# psu.net
KiCad netlist of a schematic drawn in Altium Designer
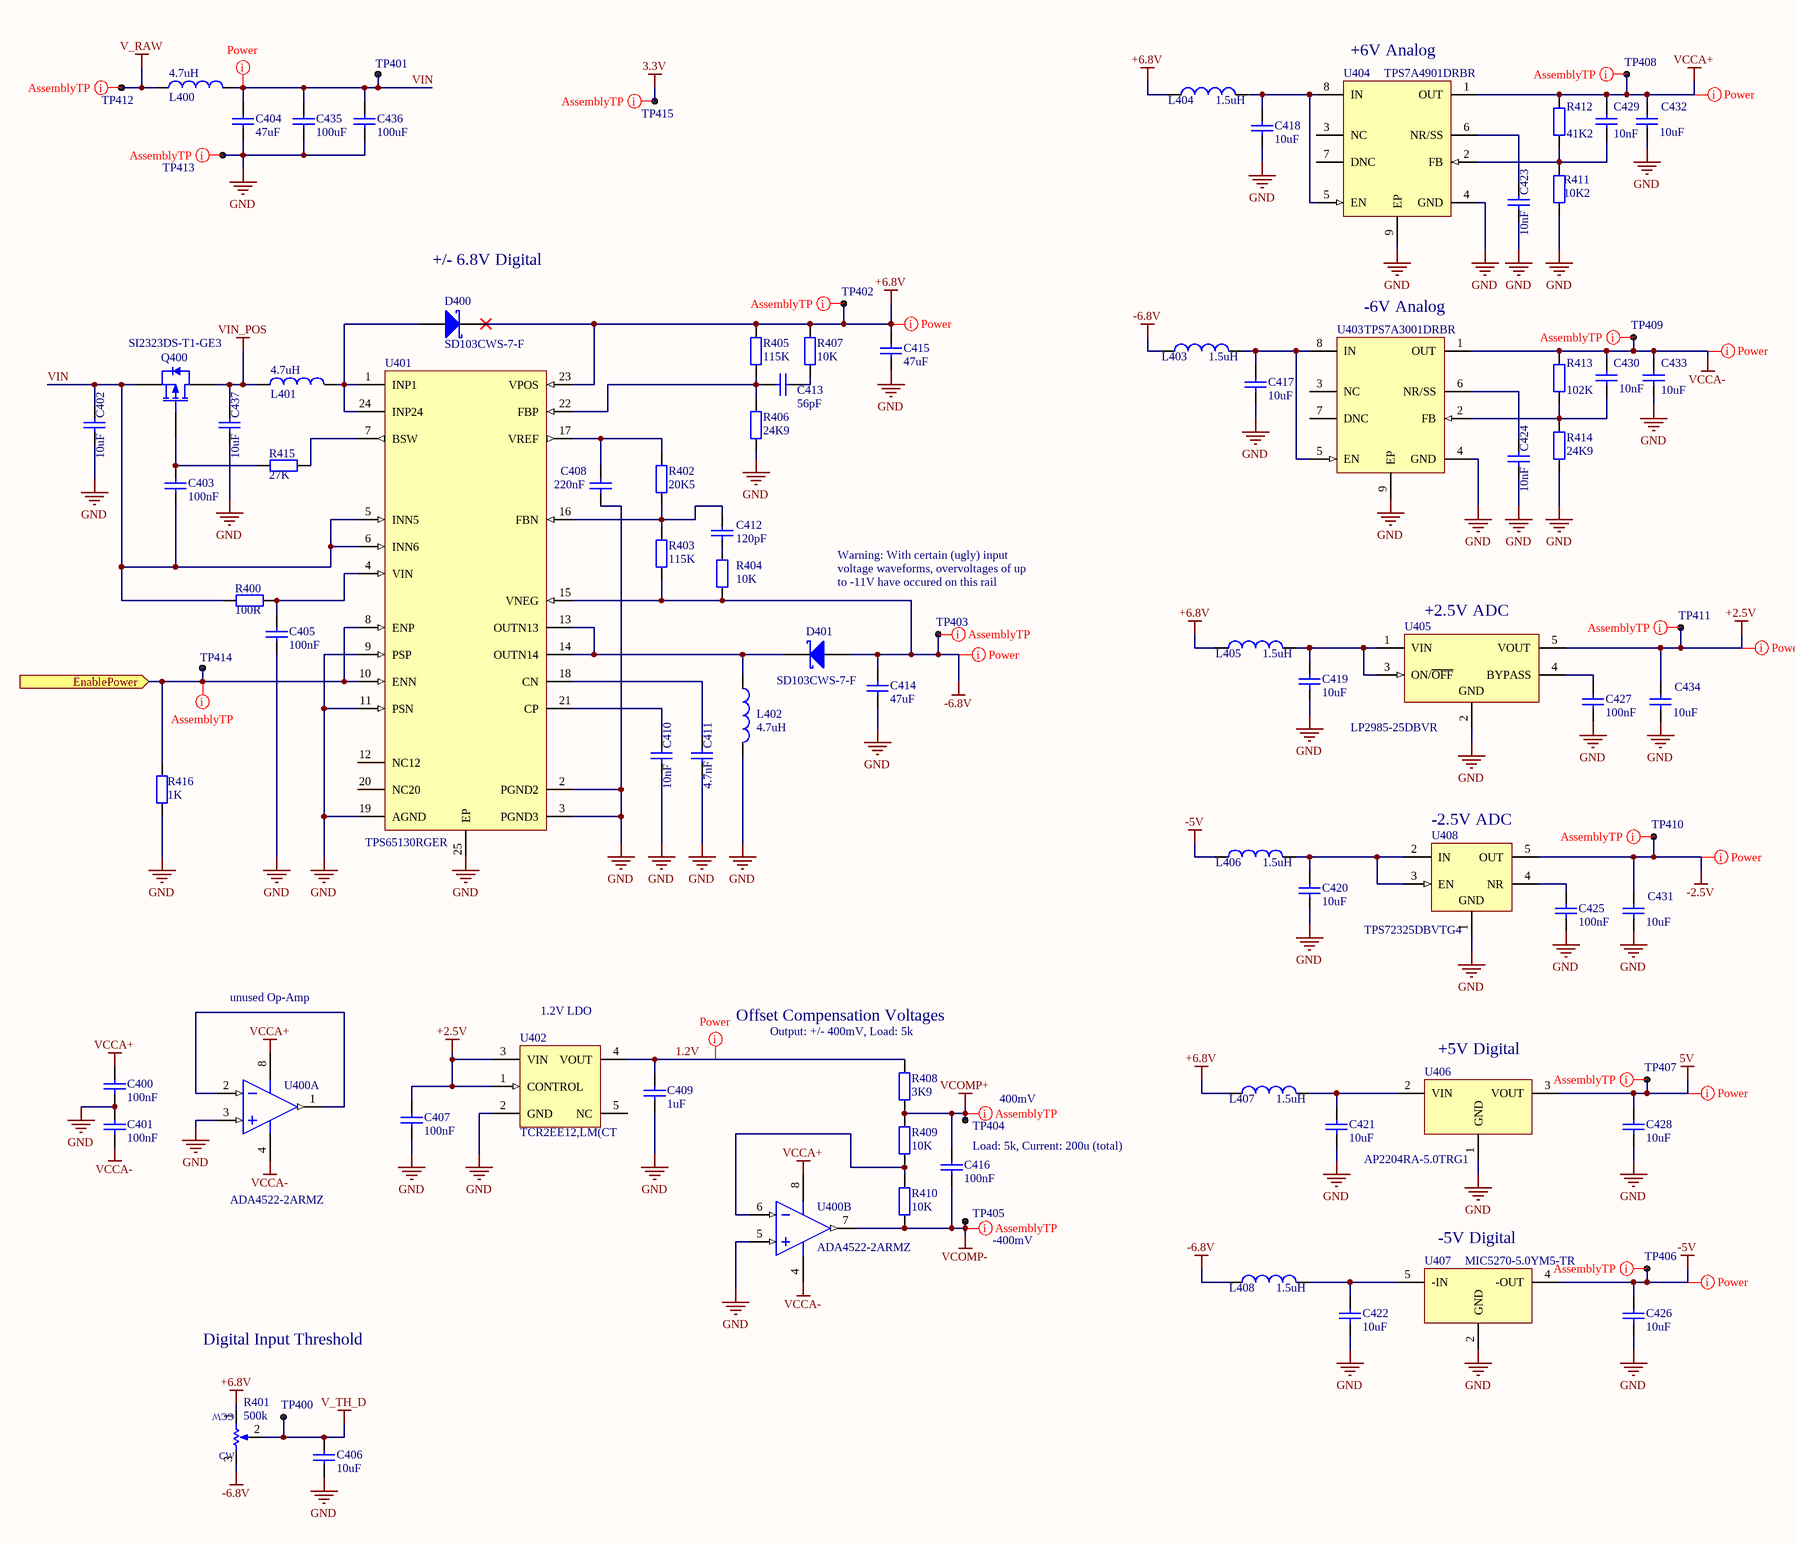
[diagram p0: psu.SchDoc]

(export (version "E")
  (design (tool "Eeschema 10.0.6"))
  (components
    (comp (ref "C400")
      (value "100nF")
      (footprint "CAPC0402(1005)60_L")
      (description "CAP 100nF 16V -20% to +80% 0402 (1005 Metric) Thickness 0.6mm SMD")
      (fields (field (name "TOLERANCE") "-20% to +80%"))
      (libsource (lib "Altium Content Vault") (part "CMP-1034-02071-1"))
    )
    (comp (ref "C401")
      (value "100nF")
      (footprint "CAPC0402(1005)60_L")
      (description "CAP 100nF 16V -20% to +80% 0402 (1005 Metric) Thickness 0.6mm SMD")
      (fields (field (name "TOLERANCE") "-20% to +80%"))
      (libsource (lib "Altium Content Vault") (part "CMP-1034-02071-1"))
    )
    (comp (ref "C402")
      (value "10uF")
      (footprint "CAPC0603(1608)100_L")
      (description "CAP 10uF 10V ±20% 0603 (1608 Metric) Thickness 1mm SMD")
      (fields (field (name "TOLERANCE") "Â±20%"))
      (libsource (lib "Altium Content Vault") (part "CMP-1035-02800-1"))
    )
    (comp (ref "C403")
      (value "100nF")
      (footprint "CAPC0402(1005)60_L")
      (description "CAP 100nF 16V -20% to +80% 0402 (1005 Metric) Thickness 0.6mm SMD")
      (fields (field (name "TOLERANCE") "-20% to +80%"))
      (libsource (lib "Altium Content Vault") (part "CMP-1034-02071-1"))
    )
    (comp (ref "C404")
      (value "47uF")
      (footprint "CAPC1210(3225)280_L")
      (description "CAP 47uF 16V ±20% 1210 (3225 Metric) Thickness 2.8mm SMD")
      (fields (field (name "TOLERANCE") "Â±20%"))
      (libsource (lib "Altium Content Vault") (part "CMP-1038-02296-1"))
    )
    (comp (ref "C405")
      (value "100nF")
      (footprint "CAPC0402(1005)60_L")
      (description "CAP 100nF 16V -20% to +80% 0402 (1005 Metric) Thickness 0.6mm SMD")
      (fields (field (name "TOLERANCE") "-20% to +80%"))
      (libsource (lib "Altium Content Vault") (part "CMP-1034-02071-1"))
    )
    (comp (ref "C406")
      (value "10uF")
      (footprint "CAPC0603(1608)100_L")
      (description "CAP 10uF 10V ±20% 0603 (1608 Metric) Thickness 1mm SMD")
      (fields (field (name "TOLERANCE") "Â±20%"))
      (libsource (lib "Altium Content Vault") (part "CMP-1035-02800-1"))
    )
    (comp (ref "C407")
      (value "100nF")
      (footprint "CAPC0402(1005)60_L")
      (description "CAP 100nF 16V -20% to +80% 0402 (1005 Metric) Thickness 0.6mm SMD")
      (fields (field (name "TOLERANCE") "-20% to +80%"))
      (libsource (lib "Altium Content Vault") (part "CMP-1034-02071-1"))
    )
    (comp (ref "C408")
      (value "220nF")
      (footprint "CAPC0402(1005)60_L")
      (description "CAP 220nF 10V -20% to +80% 0402 (1005 Metric) Thickness 0.6mm SMD")
      (fields (field (name "TOLERANCE") "-20% to +80%"))
      (libsource (lib "Altium Content Vault") (part "CMP-1034-02088-1"))
    )
    (comp (ref "C409")
      (value "1uF")
      (footprint "CAPC0402(1005)60_L")
      (description "CAP 1uF 16V ±20% 0402 (1005 Metric) Thickness 0.6mm SMD")
      (fields (field (name "TOLERANCE") "Â±20%"))
      (libsource (lib "Altium Content Vault") (part "CAP"))
    )
    (comp (ref "C410")
      (value "10nF")
      (footprint "CAPC0402(1005)60_L")
      (description "CAP 10nF 25V ±5% 0402 (1005 Metric) Thickness 0.6mm SMD")
      (fields (field (name "TOLERANCE") "Â±5%"))
      (libsource (lib "Altium Content Vault") (part "CAP"))
    )
    (comp (ref "C411")
      (value "4.7nF")
      (footprint "CAPC0402(1005)60_L")
      (description "CAP 4.7nF 50V ±20% 0402 (1005 Metric) Thickness 0.6mm SMD")
      (fields (field (name "TOLERANCE") "Â±20%"))
      (libsource (lib "Altium Content Vault") (part "CAP"))
    )
    (comp (ref "C412")
      (value "120pF")
      (footprint "CAPC0402(1005)60_L")
      (description "CAP 120pF 50V ±5% 0402 (1005 Metric) Thickness 0.6mm SMD")
      (fields (field (name "TOLERANCE") "Â±5%"))
      (libsource (lib "Altium Content Vault") (part "CAP"))
    )
    (comp (ref "C413")
      (value "56pF")
      (footprint "CAPC0402(1005)60_L")
      (description "CAP 56pF 50V ±5% 0402 (1005 Metric) Thickness 0.6mm SMD")
      (fields (field (name "TOLERANCE") "Â±5%"))
      (libsource (lib "Altium Content Vault") (part "CAP"))
    )
    (comp (ref "C414")
      (value "47uF")
      (footprint "CAPC1210(3225)280_L")
      (description "CAP 47uF 16V ±20% 1210 (3225 Metric) Thickness 2.8mm SMD")
      (fields (field (name "TOLERANCE") "Â±20%"))
      (libsource (lib "Altium Content Vault") (part "CMP-1038-02296-1"))
    )
    (comp (ref "C415")
      (value "47uF")
      (footprint "CAPC1210(3225)280_L")
      (description "CAP 47uF 16V ±20% 1210 (3225 Metric) Thickness 2.8mm SMD")
      (fields (field (name "TOLERANCE") "Â±20%"))
      (libsource (lib "Altium Content Vault") (part "CMP-1038-02296-1"))
    )
    (comp (ref "C416")
      (value "100nF")
      (footprint "CAPC0402(1005)60_L")
      (description "CAP 100nF 16V -20% to +80% 0402 (1005 Metric) Thickness 0.6mm SMD")
      (fields (field (name "TOLERANCE") "-20% to +80%"))
      (libsource (lib "Altium Content Vault") (part "CMP-1034-02071-1"))
    )
    (comp (ref "C417")
      (value "10uF")
      (footprint "CAPC0603(1608)100_L")
      (description "CAP 10uF 10V ±20% 0603 (1608 Metric) Thickness 1mm SMD")
      (fields (field (name "TOLERANCE") "Â±20%"))
      (libsource (lib "Altium Content Vault") (part "CMP-1035-02800-1"))
    )
    (comp (ref "C418")
      (value "10uF")
      (footprint "CAPC0603(1608)100_L")
      (description "CAP 10uF 10V ±20% 0603 (1608 Metric) Thickness 1mm SMD")
      (fields (field (name "TOLERANCE") "Â±20%"))
      (libsource (lib "Altium Content Vault") (part "CMP-1035-02800-1"))
    )
    (comp (ref "C419")
      (value "10uF")
      (footprint "CAPC0603(1608)100_L")
      (description "CAP 10uF 10V ±20% 0603 (1608 Metric) Thickness 1mm SMD")
      (fields (field (name "TOLERANCE") "Â±20%"))
      (libsource (lib "Altium Content Vault") (part "CMP-1035-02800-1"))
    )
    (comp (ref "C420")
      (value "10uF")
      (footprint "CAPC0603(1608)100_L")
      (description "CAP 10uF 10V ±20% 0603 (1608 Metric) Thickness 1mm SMD")
      (fields (field (name "TOLERANCE") "Â±20%"))
      (libsource (lib "Altium Content Vault") (part "CMP-1035-02800-1"))
    )
    (comp (ref "C421")
      (value "10uF")
      (footprint "CAPC0603(1608)100_L")
      (description "CAP 10uF 10V ±20% 0603 (1608 Metric) Thickness 1mm SMD")
      (fields (field (name "TOLERANCE") "Â±20%"))
      (libsource (lib "Altium Content Vault") (part "CMP-1035-02800-1"))
    )
    (comp (ref "C422")
      (value "10uF")
      (footprint "CAPC0603(1608)100_L")
      (description "CAP 10uF 10V ±20% 0603 (1608 Metric) Thickness 1mm SMD")
      (fields (field (name "TOLERANCE") "Â±20%"))
      (libsource (lib "Altium Content Vault") (part "CMP-1035-02800-1"))
    )
    (comp (ref "C423")
      (value "10nF")
      (footprint "CAPC0402(1005)60_L")
      (description "CAP 10nF 25V ±5% 0402 (1005 Metric) Thickness 0.6mm SMD")
      (fields (field (name "TOLERANCE") "Â±5%"))
      (libsource (lib "Altium Content Vault") (part "CAP"))
    )
    (comp (ref "C424")
      (value "10nF")
      (footprint "CAPC0402(1005)60_L")
      (description "CAP 10nF 25V ±5% 0402 (1005 Metric) Thickness 0.6mm SMD")
      (fields (field (name "TOLERANCE") "Â±5%"))
      (libsource (lib "Altium Content Vault") (part "CAP"))
    )
    (comp (ref "C425")
      (value "100nF")
      (footprint "CAPC0402(1005)60_L")
      (description "CAP 100nF 16V -20% to +80% 0402 (1005 Metric) Thickness 0.6mm SMD")
      (fields (field (name "TOLERANCE") "-20% to +80%"))
      (libsource (lib "Altium Content Vault") (part "CMP-1034-02071-1"))
    )
    (comp (ref "C426")
      (value "10uF")
      (footprint "CAPC0603(1608)100_L")
      (description "CAP 10uF 10V ±20% 0603 (1608 Metric) Thickness 1mm SMD")
      (fields (field (name "TOLERANCE") "Â±20%"))
      (libsource (lib "Altium Content Vault") (part "CMP-1035-02800-1"))
    )
    (comp (ref "C427")
      (value "100nF")
      (footprint "CAPC0402(1005)60_L")
      (description "CAP 100nF 16V -20% to +80% 0402 (1005 Metric) Thickness 0.6mm SMD")
      (fields (field (name "TOLERANCE") "-20% to +80%"))
      (libsource (lib "Altium Content Vault") (part "CMP-1034-02071-1"))
    )
    (comp (ref "C428")
      (value "10uF")
      (footprint "CAPC0603(1608)100_L")
      (description "CAP 10uF 10V ±20% 0603 (1608 Metric) Thickness 1mm SMD")
      (fields (field (name "TOLERANCE") "Â±20%"))
      (libsource (lib "Altium Content Vault") (part "CMP-1035-02800-1"))
    )
    (comp (ref "C429")
      (value "10nF")
      (footprint "CAPC0402(1005)60_L")
      (description "CAP 10nF 25V ±5% 0402 (1005 Metric) Thickness 0.6mm SMD")
      (fields (field (name "TOLERANCE") "Â±5%"))
      (libsource (lib "Altium Content Vault") (part "CAP"))
    )
    (comp (ref "C430")
      (value "10nF")
      (footprint "CAPC0402(1005)60_L")
      (description "CAP 10nF 25V ±5% 0402 (1005 Metric) Thickness 0.6mm SMD")
      (fields (field (name "TOLERANCE") "Â±5%"))
      (libsource (lib "Altium Content Vault") (part "CAP"))
    )
    (comp (ref "C431")
      (value "10uF")
      (footprint "CAPC0603(1608)100_L")
      (description "CAP 10uF 10V ±20% 0603 (1608 Metric) Thickness 1mm SMD")
      (fields (field (name "TOLERANCE") "Â±20%"))
      (libsource (lib "Altium Content Vault") (part "CMP-1035-02800-1"))
    )
    (comp (ref "C432")
      (value "10uF")
      (footprint "CAPC0603(1608)100_L")
      (description "CAP 10uF 10V ±20% 0603 (1608 Metric) Thickness 1mm SMD")
      (fields (field (name "TOLERANCE") "Â±20%"))
      (libsource (lib "Altium Content Vault") (part "CMP-1035-02800-1"))
    )
    (comp (ref "C433")
      (value "10uF")
      (footprint "CAPC0603(1608)100_L")
      (description "CAP 10uF 10V ±20% 0603 (1608 Metric) Thickness 1mm SMD")
      (fields (field (name "TOLERANCE") "Â±20%"))
      (libsource (lib "Altium Content Vault") (part "CMP-1035-02800-1"))
    )
    (comp (ref "C434")
      (value "10uF")
      (footprint "CAPC0603(1608)100_L")
      (description "CAP 10uF 10V ±20% 0603 (1608 Metric) Thickness 1mm SMD")
      (fields (field (name "TOLERANCE") "Â±20%"))
      (libsource (lib "Altium Content Vault") (part "CMP-1035-02800-1"))
    )
    (comp (ref "C435")
      (value "100uF")
      (footprint "CAPC1210(3225)200_L")
      (description "CAP 100uF 16V ±20% 1210 (3225 Metric) SMD")
      (libsource (lib "Altium Content Vault") (part "CAP_5"))
    )
    (comp (ref "C436")
      (value "100uF")
      (footprint "CAPC1210(3225)200_L")
      (description "CAP 100uF 16V ±20% 1210 (3225 Metric) SMD")
      (libsource (lib "Altium Content Vault") (part "CAP_5"))
    )
    (comp (ref "C437")
      (value "10uF")
      (footprint "CAPC0603(1608)100_L")
      (description "CAP 10uF 10V ±20% 0603 (1608 Metric) Thickness 1mm SMD")
      (fields (field (name "TOLERANCE") "Â±20%"))
      (libsource (lib "Altium Content Vault") (part "CMP-1035-02800-1"))
    )
    (comp (ref "D400")
      (value "SD103CWS-7-F")
      (footprint "DIOD-SOD323-2_V")
      (description "DIODE SCHOTTKY 20V 350MA SOD323")
      (fields (field (name "MANUFACTURER") "Diodes Incorporated"))
      (libsource (lib "ETHZ Vault") (part "Diode Schottky"))
    )
    (comp (ref "D401")
      (value "SD103CWS-7-F")
      (footprint "DIOD-SOD323-2_V")
      (description "DIODE SCHOTTKY 20V 350MA SOD323")
      (fields (field (name "MANUFACTURER") "Diodes Incorporated"))
      (libsource (lib "ETHZ Vault") (part "Diode Schottky"))
    )
    (comp (ref "L400")
      (value "4.7uH")
      (footprint "INDC2520X10L")
      (description "FIXED IND 4.7UH 1A 110 MOHM SMD")
      (fields (field (name "TOLERANCE") "±20%") (field (name "MANUFACTURER") "TDK Corporation"))
      (libsource (lib "ETHZ Vault") (part "CMP-00119-1"))
    )
    (comp (ref "L401")
      (value "4.7uH")
      (footprint "INDC2520X10L")
      (description "FIXED IND 4.7UH 1A 110 MOHM SMD")
      (fields (field (name "TOLERANCE") "±20%") (field (name "MANUFACTURER") "TDK Corporation"))
      (libsource (lib "ETHZ Vault") (part "CMP-00119-1"))
    )
    (comp (ref "L402")
      (value "4.7uH")
      (footprint "INDC2520X10L")
      (description "FIXED IND 4.7UH 1A 110 MOHM SMD")
      (fields (field (name "TOLERANCE") "±20%") (field (name "MANUFACTURER") "TDK Corporation"))
      (libsource (lib "ETHZ Vault") (part "CMP-00119-1"))
    )
    (comp (ref "L403")
      (value "1.5uH")
      (footprint "INDC0603(1608)_L")
      (description "FIXED IND 1.5UH 50MA 700 MOHM")
      (fields (field (name "TOLERANCE") "±20%") (field (name "MANUFACTURER") "TDK Corporation"))
      (libsource (lib "ETHZ Vault") (part "CMP-00229-1"))
    )
    (comp (ref "L404")
      (value "1.5uH")
      (footprint "INDC0603(1608)_L")
      (description "FIXED IND 1.5UH 50MA 700 MOHM")
      (fields (field (name "TOLERANCE") "±20%") (field (name "MANUFACTURER") "TDK Corporation"))
      (libsource (lib "ETHZ Vault") (part "CMP-00229-1"))
    )
    (comp (ref "L405")
      (value "1.5uH")
      (footprint "INDC0603(1608)_L")
      (description "FIXED IND 1.5UH 50MA 700 MOHM")
      (fields (field (name "TOLERANCE") "±20%") (field (name "MANUFACTURER") "TDK Corporation"))
      (libsource (lib "ETHZ Vault") (part "CMP-00229-1"))
    )
    (comp (ref "L406")
      (value "1.5uH")
      (footprint "INDC0603(1608)_L")
      (description "FIXED IND 1.5UH 50MA 700 MOHM")
      (fields (field (name "TOLERANCE") "±20%") (field (name "MANUFACTURER") "TDK Corporation"))
      (libsource (lib "ETHZ Vault") (part "CMP-00229-1"))
    )
    (comp (ref "L407")
      (value "1.5uH")
      (footprint "INDC0603(1608)_L")
      (description "FIXED IND 1.5UH 50MA 700 MOHM")
      (fields (field (name "TOLERANCE") "±20%") (field (name "MANUFACTURER") "TDK Corporation"))
      (libsource (lib "ETHZ Vault") (part "CMP-00229-1"))
    )
    (comp (ref "L408")
      (value "1.5uH")
      (footprint "INDC0603(1608)_L")
      (description "FIXED IND 1.5UH 50MA 700 MOHM")
      (fields (field (name "TOLERANCE") "±20%") (field (name "MANUFACTURER") "TDK Corporation"))
      (libsource (lib "ETHZ Vault") (part "CMP-00229-1"))
    )
    (comp (ref "Q400")
      (value "SI2323DS-T1-GE3")
      (footprint "SOT-23-TT3_N")
      (description "MOSFET P-CH 20V 3.7A SOT23-3")
      (fields (field (name "MANUFACTURER") "Vishay Siliconix"))
      (libsource (lib "ETHZ Vault") (part "MOSFET P Channel"))
    )
    (comp (ref "R400")
      (value "100R")
      (footprint "RESC0402(1005)_L")
      (description "100R 0.063W 1% 0402 (1005 Metric)  SMD")
      (fields (field (name "TOLERANCE") "1 %") (field (name "POWER") "0.063 W"))
      (libsource (lib "Altium Content Vault") (part "CMP-1011-00397-1"))
    )
    (comp (ref "R401")
      (value "500k")
      (footprint "43W")
      (description "TRIMMER 500K OHM 0.125W SMD")
      (fields (field (name "TOLERANCE") "±20%") (field (name "MANUFACTURER") "TT Electronics/BI"))
      (libsource (lib "ETHZ Vault") (part "Trimmer"))
    )
    (comp (ref "R402")
      (value "20K5")
      (footprint "RESC0402(1005)_L")
      (description "20K5 0.063W 1% 0402 (1005 Metric)  SMD")
      (fields (field (name "POWER") "0.063 W") (field (name "TOLERANCE") "1 %"))
      (libsource (lib "Altium Content Vault") (part "RES"))
    )
    (comp (ref "R403")
      (value "115K")
      (footprint "RESC0402(1005)_L")
      (description "115K 0.063W 1% 0402 (1005 Metric)  SMD")
      (fields (field (name "TOLERANCE") "1 %") (field (name "POWER") "0.063 W"))
      (libsource (lib "") (part "RES_1"))
    )
    (comp (ref "R404")
      (value "10K")
      (footprint "RESC0402(1005)_L")
      (description "10K 0.063W 1% 0402 (1005 Metric)  SMD")
      (fields (field (name "TOLERANCE") "1 %") (field (name "POWER") "0.063 W"))
      (libsource (lib "Altium Content Vault") (part "CMP-1011-00623-1"))
    )
    (comp (ref "R405")
      (value "115K")
      (footprint "RESC0402(1005)_L")
      (description "115K 0.063W 1% 0402 (1005 Metric)  SMD")
      (fields (field (name "TOLERANCE") "1 %") (field (name "POWER") "0.063 W"))
      (libsource (lib "Altium Content Vault") (part "RES"))
    )
    (comp (ref "R406")
      (value "24K9")
      (footprint "RESC0402(1005)_L")
      (description "24K9 0.063W 1% 0402 (1005 Metric)  SMD")
      (fields (field (name "TOLERANCE") "1 %") (field (name "POWER") "0.063 W"))
      (libsource (lib "Altium Content Vault") (part "RES"))
    )
    (comp (ref "R407")
      (value "10K")
      (footprint "RESC0402(1005)_L")
      (description "10K 0.063W 1% 0402 (1005 Metric)  SMD")
      (fields (field (name "TOLERANCE") "1 %") (field (name "POWER") "0.063 W"))
      (libsource (lib "Altium Content Vault") (part "CMP-1011-00623-1"))
    )
    (comp (ref "R408")
      (value "3K9")
      (footprint "RESC0402(1005)_L")
      (description "3K9 0.063W 1% 0402 (1005 Metric)  SMD")
      (fields (field (name "TOLERANCE") "1 %") (field (name "POWER") "0.063 W"))
      (libsource (lib "Altium Content Vault") (part "RES"))
    )
    (comp (ref "R409")
      (value "10K")
      (footprint "RESC0402(1005)_L")
      (description "10K 0.063W 1% 0402 (1005 Metric)  SMD")
      (fields (field (name "TOLERANCE") "1 %") (field (name "POWER") "0.063 W"))
      (libsource (lib "Altium Content Vault") (part "RES"))
    )
    (comp (ref "R410")
      (value "10K")
      (footprint "RESC0402(1005)_L")
      (description "10K 0.063W 1% 0402 (1005 Metric)  SMD")
      (fields (field (name "TOLERANCE") "1 %") (field (name "POWER") "0.063 W"))
      (libsource (lib "Altium Content Vault") (part "RES"))
    )
    (comp (ref "R411")
      (value "10K2")
      (footprint "RESC0402(1005)_L")
      (description "10K2 0.063W 1% 0402 (1005 Metric)  SMD")
      (fields (field (name "POWER") "0.063 W") (field (name "TOLERANCE") "1 %"))
      (libsource (lib "Altium Content Vault") (part "CMP-1011-00624-1"))
    )
    (comp (ref "R412")
      (value "41K2")
      (footprint "RESC0402(1005)_L")
      (description "41K2 0.063W 1% 0402 (1005 Metric)  SMD")
      (fields (field (name "TOLERANCE") "1 %") (field (name "POWER") "0.063 W"))
      (libsource (lib "Altium Content Vault") (part "CMP-1011-00692-1"))
    )
    (comp (ref "R413")
      (value "102K")
      (footprint "RESC0402(1005)_L")
      (description "102K 0.063W 1% 0402 (1005 Metric)  SMD")
      (fields (field (name "TOLERANCE") "1 %") (field (name "POWER") "0.063 W"))
      (libsource (lib "Altium Content Vault") (part "CMP-1011-00737-1"))
    )
    (comp (ref "R414")
      (value "24K9")
      (footprint "RESC0402(1005)_L")
      (description "24K9 0.063W 1% 0402 (1005 Metric)  SMD")
      (fields (field (name "TOLERANCE") "1 %") (field (name "POWER") "0.063 W"))
      (libsource (lib "Altium Content Vault") (part "CMP-1011-00666-1"))
    )
    (comp (ref "R415")
      (value "27K")
      (footprint "RESC0402(1005)_L")
      (description "27K 0.063W 1% 0402 (1005 Metric)  SMD")
      (fields (field (name "TOLERANCE") "1 %") (field (name "POWER") "0.063 W"))
      (libsource (lib "Altium Content Vault") (part "CMP-1011-00670-1"))
    )
    (comp (ref "R416")
      (value "1K")
      (footprint "RESC0402(1005)_L")
      (description "1K 0.063W 1% 0402 (1005 Metric)  SMD")
      (fields (field (name "TOLERANCE") "1 %") (field (name "POWER") "0.063 W"))
      (libsource (lib "Altium Content Vault") (part "RES"))
    )
    (comp (ref "TP400")
      (value "~")
      (footprint "Pad-0.6mm")
      (description "0.6mm SMT Test Pad")
      (libsource (lib "ETHZ Vault") (part "Test Pad"))
    )
    (comp (ref "TP401")
      (value "~")
      (footprint "Pad-0.6mm")
      (description "0.6mm SMT Test Pad")
      (libsource (lib "ETHZ Vault") (part "Test Pad"))
    )
    (comp (ref "TP402")
      (value "~")
      (footprint "Pad-0.6mm")
      (description "0.6mm SMT Test Pad")
      (libsource (lib "ETHZ Vault") (part "Test Pad"))
    )
    (comp (ref "TP403")
      (value "~")
      (footprint "Pad-0.6mm")
      (description "0.6mm SMT Test Pad")
      (libsource (lib "ETHZ Vault") (part "Test Pad"))
    )
    (comp (ref "TP404")
      (value "~")
      (footprint "Pad-0.6mm")
      (description "0.6mm SMT Test Pad")
      (libsource (lib "ETHZ Vault") (part "Test Pad"))
    )
    (comp (ref "TP405")
      (value "~")
      (footprint "Pad-0.6mm")
      (description "0.6mm SMT Test Pad")
      (libsource (lib "ETHZ Vault") (part "Test Pad"))
    )
    (comp (ref "TP406")
      (value "~")
      (footprint "Pad-0.6mm")
      (description "0.6mm SMT Test Pad")
      (libsource (lib "ETHZ Vault") (part "Test Pad"))
    )
    (comp (ref "TP407")
      (value "~")
      (footprint "Pad-0.6mm")
      (description "0.6mm SMT Test Pad")
      (libsource (lib "ETHZ Vault") (part "Test Pad"))
    )
    (comp (ref "TP408")
      (value "~")
      (footprint "Pad-0.6mm")
      (description "0.6mm SMT Test Pad")
      (libsource (lib "ETHZ Vault") (part "Test Pad"))
    )
    (comp (ref "TP409")
      (value "~")
      (footprint "Pad-0.6mm")
      (description "0.6mm SMT Test Pad")
      (libsource (lib "ETHZ Vault") (part "Test Pad"))
    )
    (comp (ref "TP410")
      (value "~")
      (footprint "Pad-0.6mm")
      (description "0.6mm SMT Test Pad")
      (libsource (lib "ETHZ Vault") (part "Test Pad"))
    )
    (comp (ref "TP411")
      (value "~")
      (footprint "Pad-0.6mm")
      (description "0.6mm SMT Test Pad")
      (libsource (lib "ETHZ Vault") (part "Test Pad"))
    )
    (comp (ref "TP412")
      (value "~")
      (footprint "Pad-0.6mm")
      (description "0.6mm SMT Test Pad")
      (libsource (lib "ETHZ Vault") (part "Test Pad"))
    )
    (comp (ref "TP413")
      (value "~")
      (footprint "Pad-0.6mm")
      (description "0.6mm SMT Test Pad")
      (libsource (lib "ETHZ Vault") (part "Test Pad"))
    )
    (comp (ref "TP414")
      (value "~")
      (footprint "Pad-0.6mm")
      (description "0.6mm SMT Test Pad")
      (libsource (lib "ETHZ Vault") (part "Test Pad"))
    )
    (comp (ref "TP415")
      (value "~")
      (footprint "Pad-0.6mm")
      (description "0.6mm SMT Test Pad")
      (libsource (lib "ETHZ Vault") (part "Test Pad"))
    )
    (comp (ref "U400")
      (value "ADA4522-2ARMZ")
      (footprint "ADI-RM-8_L")
      (description "SP Amp Zero Drift Amplifier Dual R-R I/O ±27.5V/55V 8-Pin MSOP")
      (fields (field (name "MANUFACTURER") "Analog Devices Inc."))
      (libsource (lib "ETHZ Vault") (part "TLV1702"))
    )
    (comp (ref "U401")
      (value "TPS65130RGER")
      (footprint "LT-UF-24_L")
      (description "Conv DC-DC Dual Inv/Step Up 2.7V to 5.5V 24-Pin VQFN EP")
      (fields (field (name "MANUFACTURER") "Texas Instruments"))
      (libsource (lib "ETHZ Vault") (part "TPS65130"))
    )
    (comp (ref "U402")
      (value "TCR2EE12,LM(CT")
      (footprint "TI-DRL5_L")
      (description "IC REG LDO 1.2V 0.2A ESV")
      (fields (field (name "MANUFACTURER") "Toshiba Semiconductor and Storage"))
      (libsource (lib "ETHZ Vault") (part "TCR2EE12,LM(CT"))
    )
    (comp (ref "U403")
      (value "TPS7A3001DRBR")
      (footprint "DRB8-1750X1500TP")
      (fields (field (name "MANUFACTURER") "Texas Instruments"))
      (libsource (lib "ETHZ Vault") (part "TPS7A30"))
    )
    (comp (ref "U404")
      (value "TPS7A4901DRBR")
      (footprint "DRB8-1750X1500TP")
      (fields (field (name "MANUFACTURER") "Texas Instruments"))
      (libsource (lib "ETHZ Vault") (part "TPS7A30"))
    )
    (comp (ref "U405")
      (value "LP2985-25DBVR")
      (footprint "DBV0005A_L")
      (fields (field (name "MANUFACTURER") "Texas Instruments"))
      (libsource (lib "Altium Content Vault") (part "TI-LP2985_A-10DBV5"))
    )
    (comp (ref "U406")
      (value "AP2204RA-5.0TRG1")
      (footprint "SOT89_L")
      (description "IC REG LDO Linear Voltage Regulator Positive Fixed 1 Output 5V 150mA SOT-89-3")
      (fields (field (name "MANUFACTURER") "Diodes Incorporated"))
      (libsource (lib "ETHZ Vault") (part "AP2204RA"))
    )
    (comp (ref "U407")
      (value "MIC5270-5.0YM5-TR")
      (footprint "Z5+1_L")
      (description "IC REG LDO Linear Voltage Regulator Negative Fixed 1 Output -5V 100mA SOT-23-5")
      (fields (field (name "MANUFACTURER") "Microchip Technology"))
      (libsource (lib "ETHZ Vault") (part "MIC5270"))
    )
    (comp (ref "U408")
      (value "TPS72325DBVTG4")
      (footprint "TI-DBV5_L")
      (fields (field (name "MANUFACTURER") "Texas Instruments"))
      (libsource (lib "Altium Content Vault") (part "CMP-0394-00283-1"))
    )
  )
  (nets
    (net (code "1") (name "+2.5V") (class "Default")
      (node (ref "C407") (pin "2") (pinfunction "2_2") (pintype "passive"))
      (node (ref "C434") (pin "2") (pinfunction "2_2") (pintype "passive"))
      (node (ref "TP411") (pin "1") (pinfunction "1_1") (pintype "passive"))
      (node (ref "U402") (pin "1") (pinfunction "CONTROL_1") (pintype "input"))
      (node (ref "U402") (pin "3") (pinfunction "VIN_3") (pintype "power_in"))
      (node (ref "U405") (pin "5") (pinfunction "VOUT_5") (pintype "power_in"))
    )
    (net (code "2") (name "+6.8V") (class "Default")
      (node (ref "C415") (pin "1") (pinfunction "1_1") (pintype "passive"))
      (node (ref "D400") (pin "2") (pinfunction "K_2") (pintype "passive"))
      (node (ref "L404") (pin "1") (pinfunction "1_1") (pintype "passive"))
      (node (ref "L405") (pin "1") (pinfunction "1_1") (pintype "passive"))
      (node (ref "L407") (pin "1") (pinfunction "1_1") (pintype "passive"))
      (node (ref "R401") (pin "1") (pinfunction "CCW_1") (pintype "passive"))
      (node (ref "R405") (pin "2") (pinfunction "2_2") (pintype "passive"))
      (node (ref "R407") (pin "2") (pinfunction "2_2") (pintype "passive"))
      (node (ref "TP402") (pin "1") (pinfunction "1_1") (pintype "passive"))
      (node (ref "U401") (pin "23") (pinfunction "VPOS_23") (pintype "input"))
    )
    (net (code "3") (name "-2.5V") (class "Default")
      (node (ref "C431") (pin "2") (pinfunction "2_2") (pintype "passive"))
      (node (ref "TP410") (pin "1") (pinfunction "1_1") (pintype "passive"))
      (node (ref "U408") (pin "5") (pinfunction "OUT_5") (pintype "power_in"))
    )
    (net (code "4") (name "-5V") (class "Default")
      (node (ref "C426") (pin "2") (pinfunction "2_2") (pintype "passive"))
      (node (ref "L406") (pin "1") (pinfunction "1_1") (pintype "passive"))
      (node (ref "TP406") (pin "1") (pinfunction "1_1") (pintype "passive"))
      (node (ref "U407") (pin "4") (pinfunction "-OUT_4") (pintype "power_in"))
    )
    (net (code "5") (name "-6.8V") (class "Default")
      (node (ref "C414") (pin "1") (pinfunction "1_1") (pintype "passive"))
      (node (ref "D401") (pin "1") (pinfunction "A_1") (pintype "passive"))
      (node (ref "L403") (pin "1") (pinfunction "1_1") (pintype "passive"))
      (node (ref "L408") (pin "1") (pinfunction "1_1") (pintype "passive"))
      (node (ref "R401") (pin "3") (pinfunction "CW_3") (pintype "passive"))
      (node (ref "R403") (pin "2") (pinfunction "2_2") (pintype "passive"))
      (node (ref "R404") (pin "1") (pinfunction "1_1") (pintype "passive"))
      (node (ref "TP403") (pin "1") (pinfunction "1_1") (pintype "passive"))
      (node (ref "U401") (pin "15") (pinfunction "VNEG_15") (pintype "input"))
    )
    (net (code "6") (name "/1.2V") (class "Default")
      (node (ref "C409") (pin "2") (pinfunction "2_2") (pintype "passive"))
      (node (ref "R408") (pin "2") (pinfunction "2_2") (pintype "passive"))
      (node (ref "U402") (pin "4") (pinfunction "VOUT_4") (pintype "power_in"))
    )
    (net (code "7") (name "/EnablePower") (class "Default")
      (node (ref "R416") (pin "2") (pinfunction "2_2") (pintype "passive"))
      (node (ref "TP414") (pin "1") (pinfunction "1_1") (pintype "passive"))
      (node (ref "U401") (pin "10") (pinfunction "ENN_10") (pintype "input"))
      (node (ref "U401") (pin "8") (pinfunction "ENP_8") (pintype "input"))
    )
    (net (code "8") (name "/VIN") (class "Default")
      (node (ref "C402") (pin "2") (pinfunction "2_2") (pintype "passive"))
      (node (ref "C403") (pin "1") (pinfunction "1_1") (pintype "passive"))
      (node (ref "C404") (pin "1") (pinfunction "1_1") (pintype "passive"))
      (node (ref "C435") (pin "2") (pinfunction "2_2") (pintype "passive"))
      (node (ref "C436") (pin "2") (pinfunction "2_2") (pintype "passive"))
      (node (ref "L400") (pin "2") (pinfunction "2_2") (pintype "passive"))
      (node (ref "Q400") (pin "2") (pinfunction "S_2") (pintype "passive"))
      (node (ref "R400") (pin "2") (pinfunction "2_2") (pintype "passive"))
      (node (ref "TP401") (pin "1") (pinfunction "1_1") (pintype "passive"))
      (node (ref "U401") (pin "5") (pinfunction "INN5_5") (pintype "input"))
      (node (ref "U401") (pin "6") (pinfunction "INN6_6") (pintype "input"))
    )
    (net (code "9") (name "3.3V") (class "Default")
      (node (ref "TP415") (pin "1") (pinfunction "1_1") (pintype "passive"))
    )
    (net (code "10") (name "5V") (class "Default")
      (node (ref "C428") (pin "2") (pinfunction "2_2") (pintype "passive"))
      (node (ref "TP407") (pin "1") (pinfunction "1_1") (pintype "passive"))
      (node (ref "U406") (pin "3") (pinfunction "VOUT_3") (pintype "power_in"))
    )
    (net (code "11") (name "GND") (class "Default")
      (node (ref "C400") (pin "1") (pinfunction "1_1") (pintype "passive"))
      (node (ref "C401") (pin "2") (pinfunction "2_2") (pintype "passive"))
      (node (ref "C402") (pin "1") (pinfunction "1_1") (pintype "passive"))
      (node (ref "C404") (pin "2") (pinfunction "2_2") (pintype "passive"))
      (node (ref "C405") (pin "1") (pinfunction "1_1") (pintype "passive"))
      (node (ref "C406") (pin "1") (pinfunction "1_1") (pintype "passive"))
      (node (ref "C407") (pin "1") (pinfunction "1_1") (pintype "passive"))
      (node (ref "C408") (pin "1") (pinfunction "1_1") (pintype "passive"))
      (node (ref "C409") (pin "1") (pinfunction "1_1") (pintype "passive"))
      (node (ref "C410") (pin "1") (pinfunction "1_1") (pintype "passive"))
      (node (ref "C411") (pin "1") (pinfunction "1_1") (pintype "passive"))
      (node (ref "C414") (pin "2") (pinfunction "2_2") (pintype "passive"))
      (node (ref "C415") (pin "2") (pinfunction "2_2") (pintype "passive"))
      (node (ref "C417") (pin "1") (pinfunction "1_1") (pintype "passive"))
      (node (ref "C418") (pin "1") (pinfunction "1_1") (pintype "passive"))
      (node (ref "C419") (pin "1") (pinfunction "1_1") (pintype "passive"))
      (node (ref "C420") (pin "1") (pinfunction "1_1") (pintype "passive"))
      (node (ref "C421") (pin "1") (pinfunction "1_1") (pintype "passive"))
      (node (ref "C422") (pin "1") (pinfunction "1_1") (pintype "passive"))
      (node (ref "C423") (pin "1") (pinfunction "1_1") (pintype "passive"))
      (node (ref "C424") (pin "1") (pinfunction "1_1") (pintype "passive"))
      (node (ref "C425") (pin "1") (pinfunction "1_1") (pintype "passive"))
      (node (ref "C426") (pin "1") (pinfunction "1_1") (pintype "passive"))
      (node (ref "C427") (pin "1") (pinfunction "1_1") (pintype "passive"))
      (node (ref "C428") (pin "1") (pinfunction "1_1") (pintype "passive"))
      (node (ref "C431") (pin "1") (pinfunction "1_1") (pintype "passive"))
      (node (ref "C432") (pin "1") (pinfunction "1_1") (pintype "passive"))
      (node (ref "C433") (pin "1") (pinfunction "1_1") (pintype "passive"))
      (node (ref "C434") (pin "1") (pinfunction "1_1") (pintype "passive"))
      (node (ref "C435") (pin "1") (pinfunction "1_1") (pintype "passive"))
      (node (ref "C436") (pin "1") (pinfunction "1_1") (pintype "passive"))
      (node (ref "C437") (pin "1") (pinfunction "1_1") (pintype "passive"))
      (node (ref "L402") (pin "2") (pinfunction "2_2") (pintype "passive"))
      (node (ref "R406") (pin "1") (pinfunction "1_1") (pintype "passive"))
      (node (ref "R411") (pin "1") (pinfunction "1_1") (pintype "passive"))
      (node (ref "R414") (pin "1") (pinfunction "1_1") (pintype "passive"))
      (node (ref "R416") (pin "1") (pinfunction "1_1") (pintype "passive"))
      (node (ref "TP413") (pin "1") (pinfunction "1_1") (pintype "passive"))
      (node (ref "U400") (pin "3") (pinfunction "1IN+_3") (pintype "input"))
      (node (ref "U400") (pin "5") (pinfunction "2IN+_5") (pintype "input"))
      (node (ref "U401") (pin "11") (pinfunction "PSN_11") (pintype "input"))
      (node (ref "U401") (pin "19") (pinfunction "AGND_19") (pintype "power_in"))
      (node (ref "U401") (pin "2") (pinfunction "PGND2_2") (pintype "power_in"))
      (node (ref "U401") (pin "25") (pinfunction "EP_25") (pintype "passive"))
      (node (ref "U401") (pin "3") (pinfunction "PGND3_3") (pintype "power_in"))
      (node (ref "U401") (pin "9") (pinfunction "PSP_9") (pintype "input"))
      (node (ref "U402") (pin "2") (pinfunction "GND_2") (pintype "power_in"))
      (node (ref "U403") (pin "4") (pinfunction "GND_4") (pintype "power_in"))
      (node (ref "U403") (pin "9") (pinfunction "EP_9") (pintype "power_in"))
      (node (ref "U404") (pin "4") (pinfunction "GND_4") (pintype "power_in"))
      (node (ref "U404") (pin "9") (pinfunction "EP_9") (pintype "power_in"))
      (node (ref "U405") (pin "2") (pinfunction "GND_2") (pintype "power_in"))
      (node (ref "U406") (pin "1") (pinfunction "GND_1") (pintype "power_in"))
      (node (ref "U407") (pin "2") (pinfunction "GND_2") (pintype "power_in"))
      (node (ref "U408") (pin "1") (pinfunction "GND_1") (pintype "power_in"))
    )
    (net (code "12") (name "Net-(C412-Pad1)") (class "Default")
      (node (ref "C412") (pin "1") (pinfunction "1_1") (pintype "passive"))
      (node (ref "R404") (pin "2") (pinfunction "2_2") (pintype "passive"))
    )
    (net (code "13") (name "Net-(C413-Pad1)") (class "Default")
      (node (ref "C413") (pin "1") (pinfunction "1_1") (pintype "passive"))
      (node (ref "R407") (pin "1") (pinfunction "1_1") (pintype "passive"))
    )
    (net (code "14") (name "Net-(D400-A)") (class "Default")
      (node (ref "D400") (pin "1") (pinfunction "A_1") (pintype "passive"))
      (node (ref "L401") (pin "2") (pinfunction "2_2") (pintype "passive"))
      (node (ref "U401") (pin "1") (pinfunction "INP1_1") (pintype "power_in"))
      (node (ref "U401") (pin "24") (pinfunction "INP24_24") (pintype "power_in"))
    )
    (net (code "15") (name "Net-(D401-K)") (class "Default")
      (node (ref "D401") (pin "2") (pinfunction "K_2") (pintype "passive"))
      (node (ref "L402") (pin "1") (pinfunction "1_1") (pintype "passive"))
      (node (ref "U401") (pin "13") (pinfunction "OUTN13_13") (pintype "power_in"))
      (node (ref "U401") (pin "14") (pinfunction "OUTN14_14") (pintype "power_in"))
    )
    (net (code "16") (name "Net-(Q400-G)") (class "Default")
      (node (ref "C403") (pin "2") (pinfunction "2_2") (pintype "passive"))
      (node (ref "Q400") (pin "1") (pinfunction "G_1") (pintype "passive"))
      (node (ref "R415") (pin "1") (pinfunction "1_1") (pintype "passive"))
    )
    (net (code "17") (name "Net-(U400A-1IN-)") (class "Default")
      (node (ref "U400") (pin "1") (pinfunction "1OUT_1") (pintype "output"))
      (node (ref "U400") (pin "2") (pinfunction "1IN-_2") (pintype "input"))
    )
    (net (code "18") (name "Net-(U400B-2IN-)") (class "Default")
      (node (ref "R409") (pin "1") (pinfunction "1_1") (pintype "passive"))
      (node (ref "R410") (pin "2") (pinfunction "2_2") (pintype "passive"))
      (node (ref "U400") (pin "6") (pinfunction "2IN-_6") (pintype "input"))
    )
    (net (code "19") (name "Net-(U401-BSW)") (class "Default")
      (node (ref "R415") (pin "2") (pinfunction "2_2") (pintype "passive"))
      (node (ref "U401") (pin "7") (pinfunction "BSW_7") (pintype "output"))
    )
    (net (code "20") (name "Net-(U401-CN)") (class "Default")
      (node (ref "C411") (pin "2") (pinfunction "2_2") (pintype "passive"))
      (node (ref "U401") (pin "18") (pinfunction "CN_18") (pintype "passive"))
    )
    (net (code "21") (name "Net-(U401-CP)") (class "Default")
      (node (ref "C410") (pin "2") (pinfunction "2_2") (pintype "passive"))
      (node (ref "U401") (pin "21") (pinfunction "CP_21") (pintype "passive"))
    )
    (net (code "22") (name "Net-(U401-FBN)") (class "Default")
      (node (ref "C412") (pin "2") (pinfunction "2_2") (pintype "passive"))
      (node (ref "R402") (pin "1") (pinfunction "1_1") (pintype "passive"))
      (node (ref "R403") (pin "1") (pinfunction "1_1") (pintype "passive"))
      (node (ref "U401") (pin "16") (pinfunction "FBN_16") (pintype "input"))
    )
    (net (code "23") (name "Net-(U401-FBP)") (class "Default")
      (node (ref "C413") (pin "2") (pinfunction "2_2") (pintype "passive"))
      (node (ref "R405") (pin "1") (pinfunction "1_1") (pintype "passive"))
      (node (ref "R406") (pin "2") (pinfunction "2_2") (pintype "passive"))
      (node (ref "U401") (pin "22") (pinfunction "FBP_22") (pintype "input"))
    )
    (net (code "24") (name "Net-(U401-VIN)") (class "Default")
      (node (ref "C405") (pin "2") (pinfunction "2_2") (pintype "passive"))
      (node (ref "R400") (pin "1") (pinfunction "1_1") (pintype "passive"))
      (node (ref "U401") (pin "4") (pinfunction "VIN_4") (pintype "input"))
    )
    (net (code "25") (name "Net-(U401-VREF)") (class "Default")
      (node (ref "C408") (pin "2") (pinfunction "2_2") (pintype "passive"))
      (node (ref "R402") (pin "2") (pinfunction "2_2") (pintype "passive"))
      (node (ref "U401") (pin "17") (pinfunction "VREF_17") (pintype "output"))
    )
    (net (code "26") (name "Net-(U403-EN)") (class "Default")
      (node (ref "C417") (pin "2") (pinfunction "2_2") (pintype "passive"))
      (node (ref "L403") (pin "2") (pinfunction "2_2") (pintype "passive"))
      (node (ref "U403") (pin "5") (pinfunction "EN_5") (pintype "input"))
      (node (ref "U403") (pin "8") (pinfunction "IN_8") (pintype "power_in"))
    )
    (net (code "27") (name "Net-(U403-FB)") (class "Default")
      (node (ref "C430") (pin "1") (pinfunction "1_1") (pintype "passive"))
      (node (ref "R413") (pin "1") (pinfunction "1_1") (pintype "passive"))
      (node (ref "R414") (pin "2") (pinfunction "2_2") (pintype "passive"))
      (node (ref "U403") (pin "2") (pinfunction "FB_2") (pintype "input"))
    )
    (net (code "28") (name "Net-(U403-NR{slash}SS)") (class "Default")
      (node (ref "C424") (pin "2") (pinfunction "2_2") (pintype "passive"))
      (node (ref "U403") (pin "6") (pinfunction "NR/SS_6") (pintype "passive"))
    )
    (net (code "29") (name "Net-(U404-EN)") (class "Default")
      (node (ref "C418") (pin "2") (pinfunction "2_2") (pintype "passive"))
      (node (ref "L404") (pin "2") (pinfunction "2_2") (pintype "passive"))
      (node (ref "U404") (pin "5") (pinfunction "EN_5") (pintype "input"))
      (node (ref "U404") (pin "8") (pinfunction "IN_8") (pintype "power_in"))
    )
    (net (code "30") (name "Net-(U404-FB)") (class "Default")
      (node (ref "C429") (pin "1") (pinfunction "1_1") (pintype "passive"))
      (node (ref "R411") (pin "2") (pinfunction "2_2") (pintype "passive"))
      (node (ref "R412") (pin "1") (pinfunction "1_1") (pintype "passive"))
      (node (ref "U404") (pin "2") (pinfunction "FB_2") (pintype "input"))
    )
    (net (code "31") (name "Net-(U404-NR{slash}SS)") (class "Default")
      (node (ref "C423") (pin "2") (pinfunction "2_2") (pintype "passive"))
      (node (ref "U404") (pin "6") (pinfunction "NR/SS_6") (pintype "passive"))
    )
    (net (code "32") (name "Net-(U405-BYPASS)") (class "Default")
      (node (ref "C427") (pin "2") (pinfunction "2_2") (pintype "passive"))
      (node (ref "U405") (pin "4") (pinfunction "BYPASS_4") (pintype "passive"))
    )
    (net (code "33") (name "Net-(U405-ON{slash}~{OFF})") (class "Default")
      (node (ref "C419") (pin "2") (pinfunction "2_2") (pintype "passive"))
      (node (ref "L405") (pin "2") (pinfunction "2_2") (pintype "passive"))
      (node (ref "U405") (pin "1") (pinfunction "VIN_1") (pintype "power_in"))
      (node (ref "U405") (pin "3") (pinfunction "ON/~{OFF}_3") (pintype "input"))
    )
    (net (code "34") (name "Net-(U406-VIN)") (class "Default")
      (node (ref "C421") (pin "2") (pinfunction "2_2") (pintype "passive"))
      (node (ref "L407") (pin "2") (pinfunction "2_2") (pintype "passive"))
      (node (ref "U406") (pin "2") (pinfunction "VIN_2") (pintype "power_in"))
    )
    (net (code "35") (name "Net-(U407--IN)") (class "Default")
      (node (ref "C422") (pin "2") (pinfunction "2_2") (pintype "passive"))
      (node (ref "L408") (pin "2") (pinfunction "2_2") (pintype "passive"))
      (node (ref "U407") (pin "5") (pinfunction "-IN_5") (pintype "power_in"))
    )
    (net (code "36") (name "Net-(U408-EN)") (class "Default")
      (node (ref "C420") (pin "2") (pinfunction "2_2") (pintype "passive"))
      (node (ref "L406") (pin "2") (pinfunction "2_2") (pintype "passive"))
      (node (ref "U408") (pin "2") (pinfunction "IN_2") (pintype "power_in"))
      (node (ref "U408") (pin "3") (pinfunction "EN_3") (pintype "input"))
    )
    (net (code "37") (name "Net-(U408-NR)") (class "Default")
      (node (ref "C425") (pin "2") (pinfunction "2_2") (pintype "passive"))
      (node (ref "U408") (pin "4") (pinfunction "NR_4") (pintype "passive"))
    )
    (net (code "38") (name "VCCA+") (class "Default")
      (node (ref "C400") (pin "2") (pinfunction "2_2") (pintype "passive"))
      (node (ref "C429") (pin "2") (pinfunction "2_2") (pintype "passive"))
      (node (ref "C432") (pin "2") (pinfunction "2_2") (pintype "passive"))
      (node (ref "R412") (pin "2") (pinfunction "2_2") (pintype "passive"))
      (node (ref "TP408") (pin "1") (pinfunction "1_1") (pintype "passive"))
      (node (ref "U400") (pin "8") (pinfunction "V+_8") (pintype "power_in"))
      (node (ref "U404") (pin "1") (pinfunction "OUT_1") (pintype "power_in"))
    )
    (net (code "39") (name "VCCA-") (class "Default")
      (node (ref "C401") (pin "1") (pinfunction "1_1") (pintype "passive"))
      (node (ref "C430") (pin "2") (pinfunction "2_2") (pintype "passive"))
      (node (ref "C433") (pin "2") (pinfunction "2_2") (pintype "passive"))
      (node (ref "R413") (pin "2") (pinfunction "2_2") (pintype "passive"))
      (node (ref "TP409") (pin "1") (pinfunction "1_1") (pintype "passive"))
      (node (ref "U400") (pin "4") (pinfunction "V-_4") (pintype "power_in"))
      (node (ref "U403") (pin "1") (pinfunction "OUT_1") (pintype "power_in"))
    )
    (net (code "40") (name "VCOMP+") (class "Default")
      (node (ref "C416") (pin "2") (pinfunction "2_2") (pintype "passive"))
      (node (ref "R408") (pin "1") (pinfunction "1_1") (pintype "passive"))
      (node (ref "R409") (pin "2") (pinfunction "2_2") (pintype "passive"))
      (node (ref "TP404") (pin "1") (pinfunction "1_1") (pintype "passive"))
    )
    (net (code "41") (name "VCOMP-") (class "Default")
      (node (ref "C416") (pin "1") (pinfunction "1_1") (pintype "passive"))
      (node (ref "R410") (pin "1") (pinfunction "1_1") (pintype "passive"))
      (node (ref "TP405") (pin "1") (pinfunction "1_1") (pintype "passive"))
      (node (ref "U400") (pin "7") (pinfunction "2OUT_7") (pintype "output"))
    )
    (net (code "42") (name "VIN_POS") (class "Default")
      (node (ref "C437") (pin "2") (pinfunction "2_2") (pintype "passive"))
      (node (ref "L401") (pin "1") (pinfunction "1_1") (pintype "passive"))
      (node (ref "Q400") (pin "3") (pinfunction "D_3") (pintype "passive"))
    )
    (net (code "43") (name "V_RAW") (class "Default")
      (node (ref "L400") (pin "1") (pinfunction "1_1") (pintype "passive"))
      (node (ref "TP412") (pin "1") (pinfunction "1_1") (pintype "passive"))
    )
    (net (code "44") (name "V_TH_D") (class "Default")
      (node (ref "C406") (pin "2") (pinfunction "2_2") (pintype "passive"))
      (node (ref "R401") (pin "2") (pinfunction "WIPER_2") (pintype "passive"))
      (node (ref "TP400") (pin "1") (pinfunction "1_1") (pintype "passive"))
    )
    (net (code "45") (name "unconnected-(U401-NC12-Pad12)") (class "Default")
      (node (ref "U401") (pin "12") (pinfunction "NC12_12") (pintype "passive"))
    )
    (net (code "46") (name "unconnected-(U401-NC20-Pad20)") (class "Default")
      (node (ref "U401") (pin "20") (pinfunction "NC20_20") (pintype "passive"))
    )
    (net (code "47") (name "unconnected-(U402-NC-Pad5)") (class "Default")
      (node (ref "U402") (pin "5") (pinfunction "NC_5") (pintype "passive"))
    )
    (net (code "48") (name "unconnected-(U403-DNC-Pad7)") (class "Default")
      (node (ref "U403") (pin "7") (pinfunction "DNC_7") (pintype "passive"))
    )
    (net (code "49") (name "unconnected-(U403-NC-Pad3)") (class "Default")
      (node (ref "U403") (pin "3") (pinfunction "NC_3") (pintype "passive"))
    )
    (net (code "50") (name "unconnected-(U404-DNC-Pad7)") (class "Default")
      (node (ref "U404") (pin "7") (pinfunction "DNC_7") (pintype "passive"))
    )
    (net (code "51") (name "unconnected-(U404-NC-Pad3)") (class "Default")
      (node (ref "U404") (pin "3") (pinfunction "NC_3") (pintype "passive"))
    )
  )
)
